# design.net
KiCad netlist of a schematic drawn in EasyEDA Pro
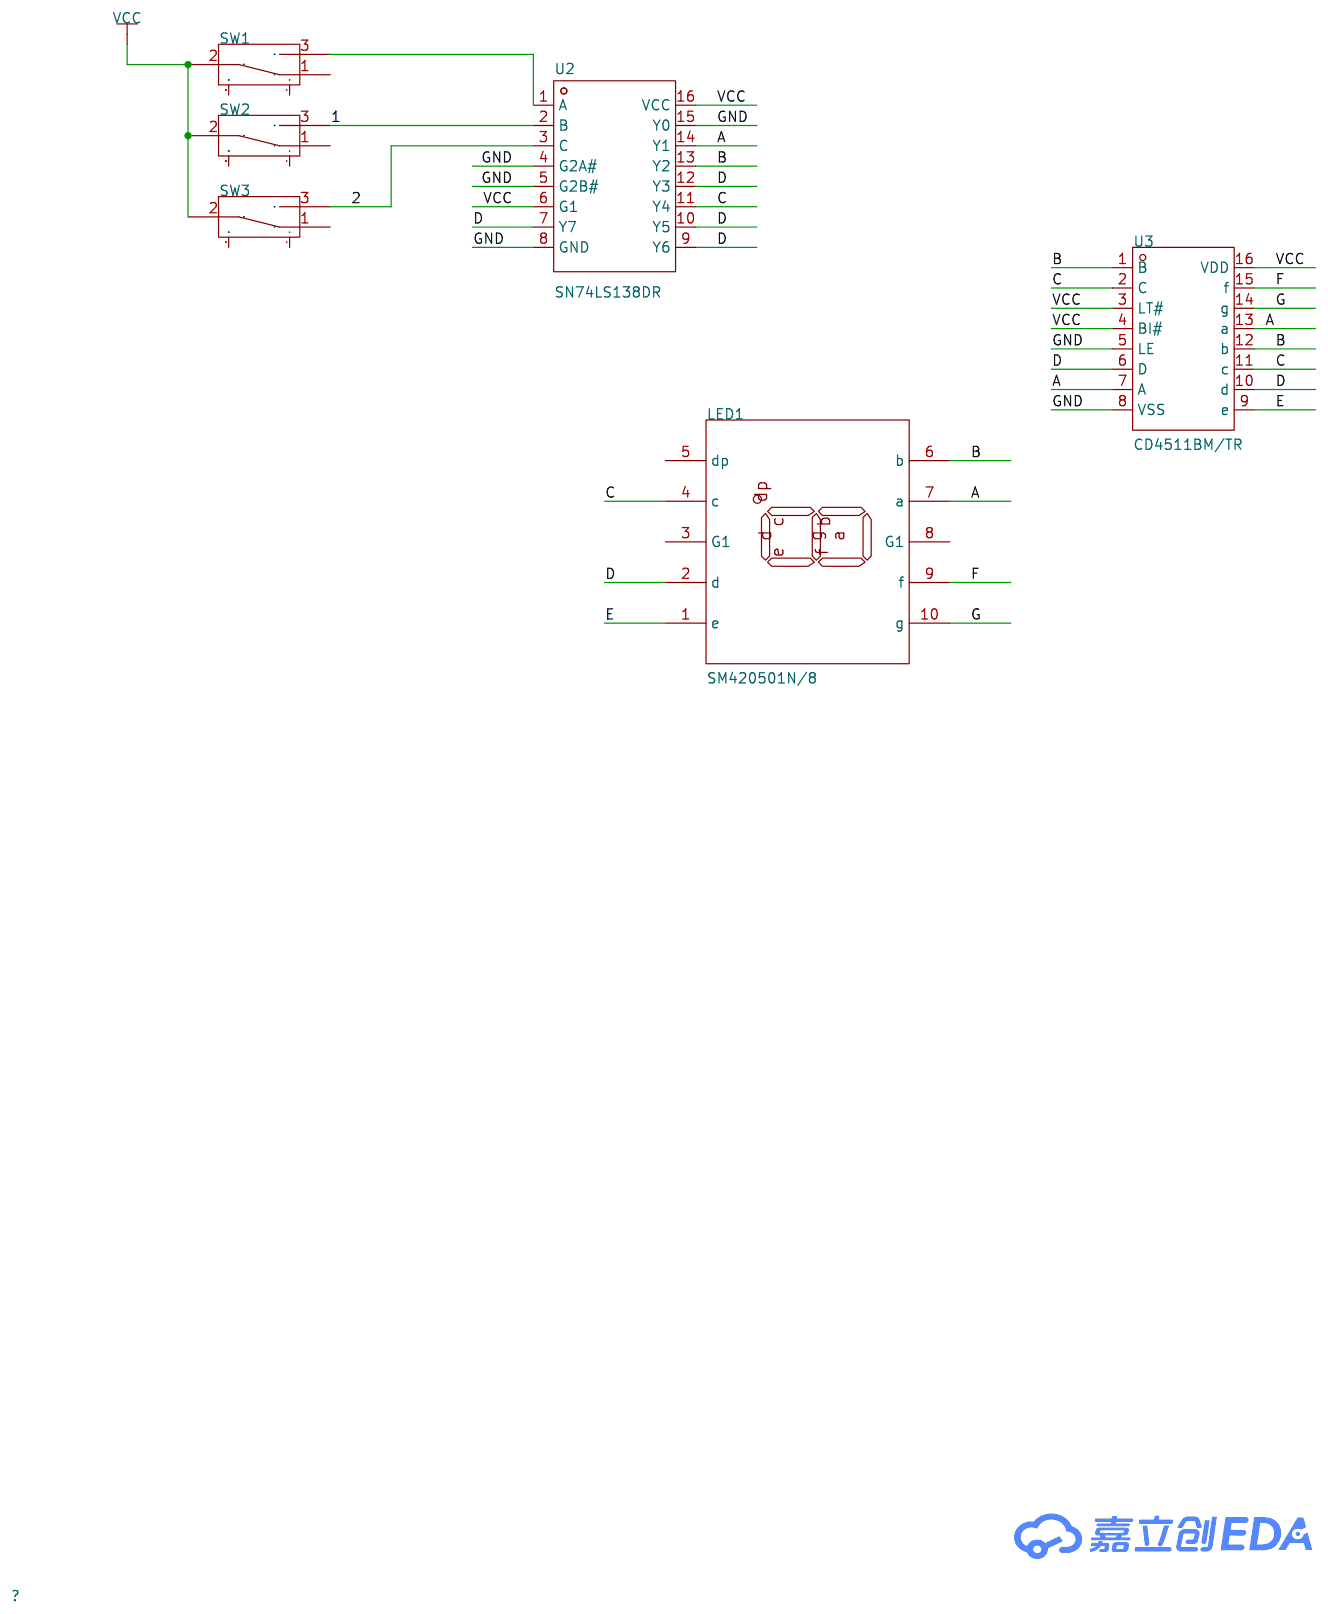
[diagram p0: schematic sheet]

(export (version "E")
  (design (tool "Eeschema 10.0.6"))
  (components
    (comp (ref "LED1")
      (value "SM420501N/8")
      (footprint "easyedapro:LED-SEG-TH_10P-L12.7-W19.0-P2.54-S15.24-BL")
      (description "数码管位数:1位;发光颜色:红色;LED极性:共阴极;数字/字母大小(英寸):0.5;")
      (fields (field (name "Manufacturer") "ARKLED(方舟)"))
      (libsource (lib "easyedapro") (part "SM420501N/8"))
    )
    (comp (ref "SW1")
      (value "~")
      (footprint "easyedapro:拨动开关_侧")
      (libsource (lib "easyedapro") (part "拨动开关"))
    )
    (comp (ref "SW2")
      (value "~")
      (footprint "easyedapro:拨动开关_侧")
      (libsource (lib "easyedapro") (part "拨动开关"))
    )
    (comp (ref "SW3")
      (value "~")
      (footprint "easyedapro:拨动开关_侧")
      (libsource (lib "easyedapro") (part "拨动开关"))
    )
    (comp (ref "U2")
      (value "SN74LS138DR")
      (footprint "easyedapro:SOIC-16_L9.9-W3.9-P1.27-LS6.0-BL")
      (description "工作电压:4.75V~5.25V;灌电流(IOL):8mA;拉电流(IOH):-;")
      (fields (field (name "Manufacturer") "TI(德州仪器)"))
      (libsource (lib "easyedapro") (part "SN74LS138DR"))
    )
    (comp (ref "U3")
      (value "CD4511BM/TR")
      (footprint "easyedapro:SOP-16_L10.0-W3.9-P1.27-LS6.0-BL")
      (fields (field (name "Manufacturer") "HGSEMI(华冠)"))
      (libsource (lib "easyedapro") (part "CD4511BM/TR"))
    )
  )
  (nets
    (net (code "1") (name "/1") (class "Default")
      (node (ref "SW2") (pin "3") (pinfunction "3_3") (pintype "input"))
      (node (ref "U2") (pin "2") (pinfunction "B_2") (pintype "unspecified"))
    )
    (net (code "2") (name "/2") (class "Default")
      (node (ref "SW3") (pin "3") (pinfunction "3_3") (pintype "input"))
      (node (ref "U2") (pin "3") (pinfunction "C_3") (pintype "unspecified"))
    )
    (net (code "3") (name "/A") (class "Default")
      (node (ref "LED1") (pin "7") (pinfunction "a_7") (pintype "input"))
      (node (ref "U2") (pin "14") (pinfunction "Y1_14") (pintype "unspecified"))
      (node (ref "U3") (pin "13") (pinfunction "a_13") (pintype "unspecified"))
      (node (ref "U3") (pin "7") (pinfunction "A_7") (pintype "unspecified"))
    )
    (net (code "4") (name "/B") (class "Default")
      (node (ref "LED1") (pin "6") (pinfunction "b_6") (pintype "input"))
      (node (ref "U2") (pin "13") (pinfunction "Y2_13") (pintype "unspecified"))
      (node (ref "U3") (pin "1") (pinfunction "B_1") (pintype "unspecified"))
      (node (ref "U3") (pin "12") (pinfunction "b_12") (pintype "unspecified"))
    )
    (net (code "5") (name "/C") (class "Default")
      (node (ref "LED1") (pin "4") (pinfunction "c_4") (pintype "input"))
      (node (ref "U2") (pin "11") (pinfunction "Y4_11") (pintype "unspecified"))
      (node (ref "U3") (pin "11") (pinfunction "c_11") (pintype "unspecified"))
      (node (ref "U3") (pin "2") (pinfunction "C_2") (pintype "unspecified"))
    )
    (net (code "6") (name "/D") (class "Default")
      (node (ref "LED1") (pin "2") (pinfunction "d_2") (pintype "input"))
      (node (ref "U2") (pin "10") (pinfunction "Y5_10") (pintype "unspecified"))
      (node (ref "U2") (pin "12") (pinfunction "Y3_12") (pintype "unspecified"))
      (node (ref "U2") (pin "7") (pinfunction "Y7_7") (pintype "unspecified"))
      (node (ref "U2") (pin "9") (pinfunction "Y6_9") (pintype "unspecified"))
      (node (ref "U3") (pin "10") (pinfunction "d_10") (pintype "unspecified"))
      (node (ref "U3") (pin "6") (pinfunction "D_6") (pintype "unspecified"))
    )
    (net (code "7") (name "/E") (class "Default")
      (node (ref "LED1") (pin "1") (pinfunction "e_1") (pintype "input"))
      (node (ref "U3") (pin "9") (pinfunction "e_9") (pintype "unspecified"))
    )
    (net (code "8") (name "/F") (class "Default")
      (node (ref "LED1") (pin "9") (pinfunction "f_9") (pintype "input"))
      (node (ref "U3") (pin "15") (pinfunction "f_15") (pintype "unspecified"))
    )
    (net (code "9") (name "/G") (class "Default")
      (node (ref "LED1") (pin "10") (pinfunction "g_10") (pintype "input"))
      (node (ref "U3") (pin "14") (pinfunction "g_14") (pintype "unspecified"))
    )
    (net (code "10") (name "/GND") (class "Default")
      (node (ref "U2") (pin "15") (pinfunction "Y0_15") (pintype "unspecified"))
      (node (ref "U2") (pin "4") (pinfunction "G2A#_4") (pintype "unspecified"))
      (node (ref "U2") (pin "5") (pinfunction "G2B#_5") (pintype "unspecified"))
      (node (ref "U2") (pin "8") (pinfunction "GND_8") (pintype "unspecified"))
      (node (ref "U3") (pin "5") (pinfunction "LE_5") (pintype "unspecified"))
      (node (ref "U3") (pin "8") (pinfunction "VSS_8") (pintype "unspecified"))
    )
    (net (code "11") (name "Net-(U2-A)") (class "Default")
      (node (ref "SW1") (pin "3") (pinfunction "3_3") (pintype "input"))
      (node (ref "U2") (pin "1") (pinfunction "A_1") (pintype "unspecified"))
    )
    (net (code "12") (name "VCC") (class "Default")
      (node (ref "SW1") (pin "2") (pinfunction "2_2") (pintype "input"))
      (node (ref "SW2") (pin "2") (pinfunction "2_2") (pintype "input"))
      (node (ref "SW3") (pin "2") (pinfunction "2_2") (pintype "input"))
      (node (ref "U2") (pin "16") (pinfunction "VCC_16") (pintype "unspecified"))
      (node (ref "U2") (pin "6") (pinfunction "G1_6") (pintype "unspecified"))
      (node (ref "U3") (pin "16") (pinfunction "VDD_16") (pintype "unspecified"))
      (node (ref "U3") (pin "3") (pinfunction "LT#_3") (pintype "unspecified"))
      (node (ref "U3") (pin "4") (pinfunction "BI#_4") (pintype "unspecified"))
    )
    (net (code "13") (name "unconnected-(LED1-G1-Pad3)") (class "Default")
      (node (ref "LED1") (pin "3") (pinfunction "G1_3") (pintype "input"))
    )
    (net (code "14") (name "unconnected-(LED1-G1-Pad8)") (class "Default")
      (node (ref "LED1") (pin "8") (pinfunction "G1_8") (pintype "input"))
    )
    (net (code "15") (name "unconnected-(LED1-dp-Pad5)") (class "Default")
      (node (ref "LED1") (pin "5") (pinfunction "dp_5") (pintype "input"))
    )
    (net (code "16") (name "unconnected-(SW1-Pad1)") (class "Default")
      (node (ref "SW1") (pin "1") (pinfunction "1_1") (pintype "input"))
    )
    (net (code "17") (name "unconnected-(SW1-Pad4)") (class "Default")
      (node (ref "SW1") (pin "4") (pinfunction "4_4") (pintype "input"))
    )
    (net (code "18") (name "unconnected-(SW1-Pad5)") (class "Default")
      (node (ref "SW1") (pin "5") (pinfunction "5_5") (pintype "input"))
    )
    (net (code "19") (name "unconnected-(SW2-Pad1)") (class "Default")
      (node (ref "SW2") (pin "1") (pinfunction "1_1") (pintype "input"))
    )
    (net (code "20") (name "unconnected-(SW2-Pad4)") (class "Default")
      (node (ref "SW2") (pin "4") (pinfunction "4_4") (pintype "input"))
    )
    (net (code "21") (name "unconnected-(SW2-Pad5)") (class "Default")
      (node (ref "SW2") (pin "5") (pinfunction "5_5") (pintype "input"))
    )
    (net (code "22") (name "unconnected-(SW3-Pad1)") (class "Default")
      (node (ref "SW3") (pin "1") (pinfunction "1_1") (pintype "input"))
    )
    (net (code "23") (name "unconnected-(SW3-Pad4)") (class "Default")
      (node (ref "SW3") (pin "4") (pinfunction "4_4") (pintype "input"))
    )
    (net (code "24") (name "unconnected-(SW3-Pad5)") (class "Default")
      (node (ref "SW3") (pin "5") (pinfunction "5_5") (pintype "input"))
    )
  )
)
